# arduinoNanoShield.net
KiCad netlist of a schematic drawn in EAGLE
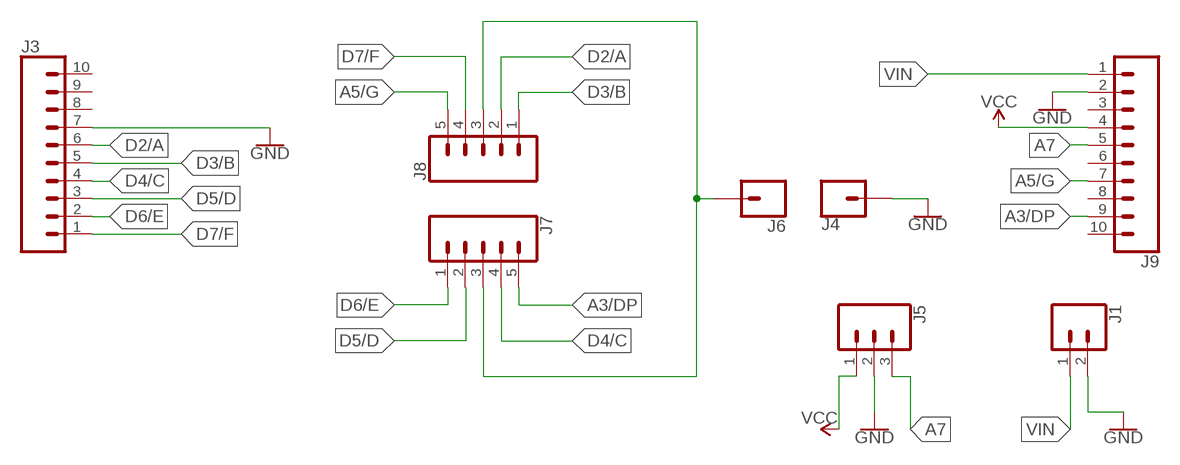
[diagram p0: schematic, sheet 1]

(export (version "E")
  (design (tool "Eeschema 10.0.6"))
  (components
    (comp (ref "J1")
      (value "CONN_02")
      (footprint "eagle-import:1X02")
      (libsource (lib "eagle-import") (part "CONN_02"))
    )
    (comp (ref "J3")
      (value "CONN_10\"")
      (footprint "eagle-import:1X10")
      (libsource (lib "eagle-import") (part "CONN_10{dblquote}"))
    )
    (comp (ref "J4")
      (value "CONN_01")
      (footprint "eagle-import:1X01")
      (libsource (lib "eagle-import") (part "CONN_01"))
    )
    (comp (ref "J5")
      (value "CONN_03")
      (footprint "eagle-import:1X03")
      (libsource (lib "eagle-import") (part "CONN_03"))
    )
    (comp (ref "J6")
      (value "CONN_01")
      (footprint "eagle-import:1X01")
      (libsource (lib "eagle-import") (part "CONN_01"))
    )
    (comp (ref "J7")
      (value "CONN_05")
      (footprint "eagle-import:1X05")
      (libsource (lib "eagle-import") (part "CONN_05"))
    )
    (comp (ref "J8")
      (value "CONN_05")
      (footprint "eagle-import:1X05")
      (libsource (lib "eagle-import") (part "CONN_05"))
    )
    (comp (ref "J9")
      (value "CONN_10\"")
      (footprint "eagle-import:1X10")
      (libsource (lib "eagle-import") (part "CONN_10{dblquote}"))
    )
  )
  (nets
    (net (code "1") (name "A3{slash}DP") (class "Default")
      (node (ref "J7") (pin "5") (pinfunction "5_5") (pintype "passive"))
      (node (ref "J9") (pin "9") (pinfunction "9_9") (pintype "passive"))
    )
    (net (code "2") (name "A5{slash}G") (class "Default")
      (node (ref "J8") (pin "5") (pinfunction "5_5") (pintype "passive"))
      (node (ref "J9") (pin "7") (pinfunction "7_7") (pintype "passive"))
    )
    (net (code "3") (name "A7") (class "Default")
      (node (ref "J5") (pin "3") (pinfunction "3_3") (pintype "passive"))
      (node (ref "J9") (pin "5") (pinfunction "5_5") (pintype "passive"))
    )
    (net (code "4") (name "D2{slash}A") (class "Default")
      (node (ref "J3") (pin "6") (pinfunction "6_6") (pintype "passive"))
      (node (ref "J8") (pin "2") (pinfunction "2_2") (pintype "passive"))
    )
    (net (code "5") (name "D3{slash}B") (class "Default")
      (node (ref "J3") (pin "5") (pinfunction "5_5") (pintype "passive"))
      (node (ref "J8") (pin "1") (pinfunction "1_1") (pintype "passive"))
    )
    (net (code "6") (name "D4{slash}C") (class "Default")
      (node (ref "J3") (pin "4") (pinfunction "4_4") (pintype "passive"))
      (node (ref "J7") (pin "4") (pinfunction "4_4") (pintype "passive"))
    )
    (net (code "7") (name "D5{slash}D") (class "Default")
      (node (ref "J3") (pin "3") (pinfunction "3_3") (pintype "passive"))
      (node (ref "J7") (pin "2") (pinfunction "2_2") (pintype "passive"))
    )
    (net (code "8") (name "D6{slash}E") (class "Default")
      (node (ref "J3") (pin "2") (pinfunction "2_2") (pintype "passive"))
      (node (ref "J7") (pin "1") (pinfunction "1_1") (pintype "passive"))
    )
    (net (code "9") (name "D7{slash}F") (class "Default")
      (node (ref "J3") (pin "1") (pinfunction "1_1") (pintype "passive"))
      (node (ref "J8") (pin "4") (pinfunction "4_4") (pintype "passive"))
    )
    (net (code "10") (name "GND") (class "Default")
      (node (ref "J1") (pin "2") (pinfunction "2_2") (pintype "passive"))
      (node (ref "J3") (pin "7") (pinfunction "7_7") (pintype "passive"))
      (node (ref "J4") (pin "1") (pinfunction "1_1") (pintype "passive"))
      (node (ref "J5") (pin "2") (pinfunction "2_2") (pintype "passive"))
      (node (ref "J9") (pin "2") (pinfunction "2_2") (pintype "passive"))
    )
    (net (code "11") (name "Net-(J6-Pad1)") (class "Default")
      (node (ref "J6") (pin "1") (pinfunction "1_1") (pintype "passive"))
      (node (ref "J7") (pin "3") (pinfunction "3_3") (pintype "passive"))
      (node (ref "J8") (pin "3") (pinfunction "3_3") (pintype "passive"))
    )
    (net (code "12") (name "VCC") (class "Default")
      (node (ref "J5") (pin "1") (pinfunction "1_1") (pintype "passive"))
      (node (ref "J9") (pin "4") (pinfunction "4_4") (pintype "passive"))
    )
    (net (code "13") (name "VIN") (class "Default")
      (node (ref "J1") (pin "1") (pinfunction "1_1") (pintype "passive"))
      (node (ref "J9") (pin "1") (pinfunction "1_1") (pintype "passive"))
    )
    (net (code "14") (name "unconnected-(J3-Pad8)") (class "Default")
      (node (ref "J3") (pin "8") (pinfunction "8_8") (pintype "passive"))
    )
    (net (code "15") (name "unconnected-(J3-Pad9)") (class "Default")
      (node (ref "J3") (pin "9") (pinfunction "9_9") (pintype "passive"))
    )
    (net (code "16") (name "unconnected-(J3-Pad10)") (class "Default")
      (node (ref "J3") (pin "10") (pinfunction "10_10") (pintype "passive"))
    )
    (net (code "17") (name "unconnected-(J9-Pad3)") (class "Default")
      (node (ref "J9") (pin "3") (pinfunction "3_3") (pintype "passive"))
    )
    (net (code "18") (name "unconnected-(J9-Pad6)") (class "Default")
      (node (ref "J9") (pin "6") (pinfunction "6_6") (pintype "passive"))
    )
    (net (code "19") (name "unconnected-(J9-Pad8)") (class "Default")
      (node (ref "J9") (pin "8") (pinfunction "8_8") (pintype "passive"))
    )
    (net (code "20") (name "unconnected-(J9-Pad10)") (class "Default")
      (node (ref "J9") (pin "10") (pinfunction "10_10") (pintype "passive"))
    )
  )
)
